# Dell_Supply_Hack_V1_0.net
KiCad netlist of a schematic drawn in EAGLE
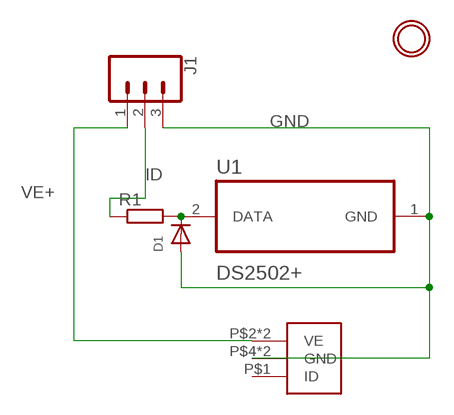
[diagram p0: schematic, sheet 1]

(export (version "E")
  (design (tool "Eeschema 10.0.6"))
  (components
    (comp (ref "D1")
      (value "DIODESOD-323F")
      (footprint "eagle-import:SOD-323F")
      (libsource (lib "eagle-import") (part "DIODESOD-323F"))
    )
    (comp (ref "J1")
      (value "CONN_03LONGPADS")
      (footprint "eagle-import:1X03_LONGPADS")
      (libsource (lib "eagle-import") (part "CONN_03LONGPADS"))
    )
    (comp (ref "R1")
      (value "R-EU_R0603")
      (footprint "eagle-import:R0603")
      (libsource (lib "eagle-import") (part "R-EU_R0603"))
    )
    (comp (ref "U$1")
      (value "DELL_CON")
      (footprint "eagle-import:DELL_CON_01")
      (libsource (lib "eagle-import") (part "DELL_CON"))
    )
    (comp (ref "U$2")
      (value "MOUNTING_HOLE")
      (footprint "eagle-import:MOUNTINGHOLE_3.0_PLATED")
      (libsource (lib "eagle-import") (part "MOUNTING_HOLE"))
    )
    (comp (ref "U1")
      (value "DS2502+")
      (footprint "eagle-import:TO92127P495H695-3")
      (fields (field (name "MF") "Maxim Integrated") (field (name "MP") "DS2502"))
      (libsource (lib "eagle-import") (part "DS2502+"))
    )
  )
  (nets
    (net (code "1") (name "/GND") (class "Default")
      (node (ref "D1") (pin "A") (pinfunction "A_A") (pintype "passive"))
      (node (ref "J1") (pin "3") (pinfunction "3_3") (pintype "passive"))
      (node (ref "U$1") (pin "P$4") (pinfunction "GND_P$4") (pintype "bidirectional"))
      (node (ref "U$1") (pin "P$5") (pinfunction "GND_P$5") (pintype "bidirectional"))
      (node (ref "U1") (pin "1") (pinfunction "GND_1") (pintype "power_in"))
    )
    (net (code "2") (name "/ID") (class "Default")
      (node (ref "J1") (pin "2") (pinfunction "2_2") (pintype "passive"))
      (node (ref "R1") (pin "1") (pinfunction "1_1") (pintype "passive"))
    )
    (net (code "3") (name "/VE+") (class "Default")
      (node (ref "J1") (pin "1") (pinfunction "1_1") (pintype "passive"))
      (node (ref "U$1") (pin "P$2") (pinfunction "VE_P$2") (pintype "bidirectional"))
      (node (ref "U$1") (pin "P$3") (pinfunction "VE_P$3") (pintype "bidirectional"))
    )
    (net (code "4") (name "Net-(U1-DATA)") (class "Default")
      (node (ref "D1") (pin "C") (pinfunction "C_C") (pintype "passive"))
      (node (ref "R1") (pin "2") (pinfunction "2_2") (pintype "passive"))
      (node (ref "U1") (pin "2") (pinfunction "DATA_2") (pintype "bidirectional"))
    )
    (net (code "5") (name "unconnected-(U$1-ID-PadP$1)") (class "Default")
      (node (ref "U$1") (pin "P$1") (pinfunction "ID_P$1") (pintype "bidirectional"))
    )
  )
)
